# slimevr_mumo_breakout_module_v1_re.net
KiCad netlist of a schematic drawn in EasyEDA Pro
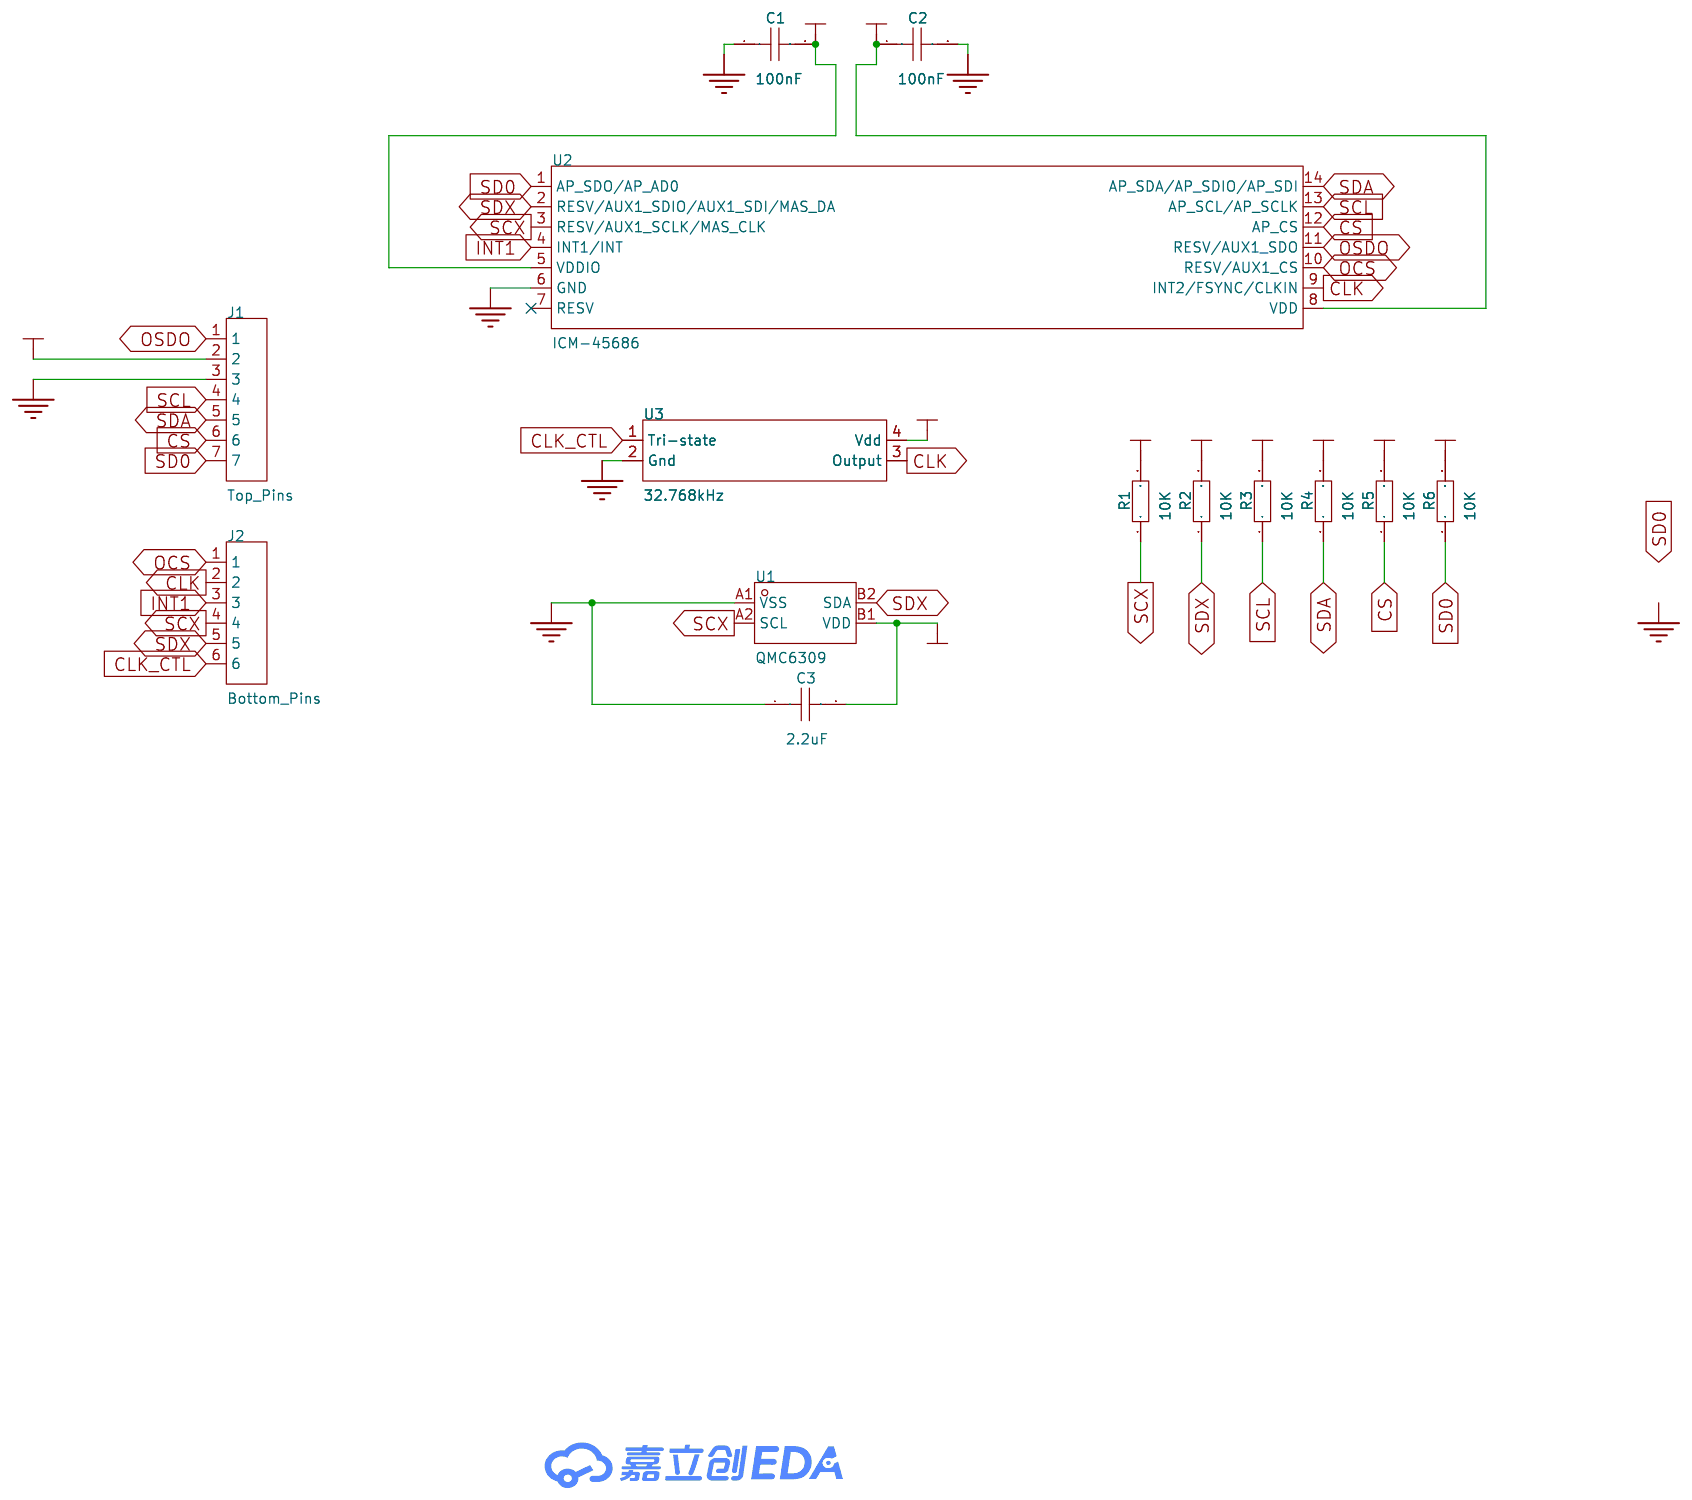
[diagram p0: schematic sheet]

(export (version "E")
  (design (tool "Eeschema 10.0.6"))
  (components
    (comp (ref "C1")
      (value "100nF")
      (footprint "easyedapro:C0603")
      (libsource (lib "easyedapro") (part "Capacitance"))
    )
    (comp (ref "C2")
      (value "100nF")
      (footprint "easyedapro:C0603")
      (libsource (lib "easyedapro") (part "Capacitance"))
    )
    (comp (ref "C3")
      (value "2.2uF")
      (footprint "easyedapro:C0603")
      (libsource (lib "easyedapro") (part "Capacitance"))
    )
    (comp (ref "J1")
      (value "Top_Pins")
      (footprint "easyedapro:HDR-TH_7P-P2.54-V-M")
      (fields
        (field (name "Manufacturer Part") "HB-PH3-25417PB2GOP")
        (field (name "Manufacturer") "HANBO(汉博)")
      )
      (libsource (lib "easyedapro") (part "HB-PH3-25417PB2GOP"))
    )
    (comp (ref "J2")
      (value "Bottom_Pins")
      (footprint "easyedapro:HDR-TH_6P-P2.54-V-M")
      (fields
        (field (name "Manufacturer Part") "HB-PH3-25416PB2GOP")
        (field (name "Manufacturer") "HANBO(汉博)")
      )
      (libsource (lib "easyedapro") (part "HB-PH3-25416PB2GOP"))
    )
    (comp (ref "R1") (value "10K") (footprint "easyedapro:R0603") (libsource (lib "easyedapro") (part "电阻")))
    (comp (ref "R2") (value "10K") (footprint "easyedapro:R0603") (libsource (lib "easyedapro") (part "电阻")))
    (comp (ref "R3") (value "10K") (footprint "easyedapro:R0603") (libsource (lib "easyedapro") (part "电阻")))
    (comp (ref "R4") (value "10K") (footprint "easyedapro:R0603") (libsource (lib "easyedapro") (part "电阻")))
    (comp (ref "R5") (value "10K") (footprint "easyedapro:R0603") (libsource (lib "easyedapro") (part "电阻")))
    (comp (ref "R6") (value "10K") (footprint "easyedapro:R0603") (libsource (lib "easyedapro") (part "电阻")))
    (comp (ref "U1")
      (value "QMC6309")
      (footprint "easyedapro:X1-WLB0808-4_L0.8-W0.8-P0.40-TL")
      (fields (field (name "Manufacturer") "QST(上海矽睿)"))
      (libsource (lib "easyedapro") (part "QMC6309"))
    )
    (comp (ref "U2")
      (value "ICM-45686")
      (footprint "easyedapro:LGA-14_L3.0-W2.5-P0.50-TL")
      (fields (field (name "Manufacturer") "TDK InvenSense(应美盛)"))
      (libsource (lib "easyedapro") (part "ICM-45686"))
    )
    (comp (ref "U3")
      (value "32.768kHz")
      (footprint "easyedapro:OSC-SMD_4P-L3.2-W2.5-BL")
      (description "频率:32.768kHz;工作电压:3.3V;工作电流:70uA;频率稳定度:±10ppm;")
      (fields
        (field (name "Manufacturer Part") "YF4032K76833T8188081")
        (field (name "Manufacturer") "JWT(晶威特)")
      )
      (libsource (lib "easyedapro") (part "YF4032K76833T8188081"))
    )
  )
  (nets
    (net (code "1") (name "+3V3") (class "Default")
      (node (ref "C1") (pin "2") (pinfunction "2_2") (pintype "input"))
      (node (ref "C2") (pin "1") (pinfunction "1_1") (pintype "input"))
      (node (ref "C3") (pin "2") (pinfunction "2_2") (pintype "input"))
      (node (ref "J1") (pin "2") (pinfunction "2_2") (pintype "unspecified"))
      (node (ref "R1") (pin "2") (pinfunction "2_2") (pintype "input"))
      (node (ref "R2") (pin "2") (pinfunction "2_2") (pintype "input"))
      (node (ref "R3") (pin "2") (pinfunction "2_2") (pintype "input"))
      (node (ref "R4") (pin "2") (pinfunction "2_2") (pintype "input"))
      (node (ref "R5") (pin "2") (pinfunction "2_2") (pintype "input"))
      (node (ref "R6") (pin "2") (pinfunction "2_2") (pintype "input"))
      (node (ref "U1") (pin "B1") (pinfunction "VDD_B1") (pintype "unspecified"))
      (node (ref "U2") (pin "5") (pinfunction "VDDIO_5") (pintype "unspecified"))
      (node (ref "U2") (pin "8") (pinfunction "VDD_8") (pintype "unspecified"))
      (node (ref "U3") (pin "4") (pinfunction "Vdd_4") (pintype "unspecified"))
    )
    (net (code "2") (name "CLK") (class "Default")
      (node (ref "J2") (pin "2") (pinfunction "2_2") (pintype "unspecified"))
      (node (ref "U2") (pin "9") (pinfunction "INT2/FSYNC/CLKIN_9") (pintype "unspecified"))
      (node (ref "U3") (pin "3") (pinfunction "Output_3") (pintype "unspecified"))
    )
    (net (code "3") (name "CLK_CTL") (class "Default")
      (node (ref "J2") (pin "6") (pinfunction "6_6") (pintype "unspecified"))
      (node (ref "U3") (pin "1") (pinfunction "Tri-state_1") (pintype "unspecified"))
    )
    (net (code "4") (name "CS") (class "Default")
      (node (ref "J1") (pin "6") (pinfunction "6_6") (pintype "unspecified"))
      (node (ref "R5") (pin "1") (pinfunction "1_1") (pintype "input"))
      (node (ref "U2") (pin "12") (pinfunction "AP_CS_12") (pintype "unspecified"))
    )
    (net (code "5") (name "GND") (class "Default")
      (node (ref "C1") (pin "1") (pinfunction "1_1") (pintype "input"))
      (node (ref "C2") (pin "2") (pinfunction "2_2") (pintype "input"))
      (node (ref "C3") (pin "1") (pinfunction "1_1") (pintype "input"))
      (node (ref "J1") (pin "3") (pinfunction "3_3") (pintype "unspecified"))
      (node (ref "U1") (pin "A1") (pinfunction "VSS_A1") (pintype "unspecified"))
      (node (ref "U2") (pin "6") (pinfunction "GND_6") (pintype "unspecified"))
      (node (ref "U3") (pin "2") (pinfunction "Gnd_2") (pintype "unspecified"))
    )
    (net (code "6") (name "INT1") (class "Default")
      (node (ref "J2") (pin "3") (pinfunction "3_3") (pintype "unspecified"))
      (node (ref "U2") (pin "4") (pinfunction "INT1/INT_4") (pintype "unspecified"))
    )
    (net (code "7") (name "OCS") (class "Default")
      (node (ref "J2") (pin "1") (pinfunction "1_1") (pintype "unspecified"))
      (node (ref "U2") (pin "10") (pinfunction "RESV/AUX1_CS_10") (pintype "unspecified"))
    )
    (net (code "8") (name "OSDO") (class "Default")
      (node (ref "J1") (pin "1") (pinfunction "1_1") (pintype "unspecified"))
      (node (ref "U2") (pin "11") (pinfunction "RESV/AUX1_SDO_11") (pintype "unspecified"))
    )
    (net (code "9") (name "SCL") (class "Default")
      (node (ref "J1") (pin "4") (pinfunction "4_4") (pintype "unspecified"))
      (node (ref "R3") (pin "1") (pinfunction "1_1") (pintype "input"))
      (node (ref "U2") (pin "13") (pinfunction "AP_SCL/AP_SCLK_13") (pintype "unspecified"))
    )
    (net (code "10") (name "SCX") (class "Default")
      (node (ref "J2") (pin "4") (pinfunction "4_4") (pintype "unspecified"))
      (node (ref "R1") (pin "1") (pinfunction "1_1") (pintype "input"))
      (node (ref "U1") (pin "A2") (pinfunction "SCL_A2") (pintype "unspecified"))
      (node (ref "U2") (pin "3") (pinfunction "RESV/AUX1_SCLK/MAS_CLK_3") (pintype "unspecified"))
    )
    (net (code "11") (name "SD0") (class "Default")
      (node (ref "J1") (pin "7") (pinfunction "7_7") (pintype "unspecified"))
      (node (ref "R6") (pin "1") (pinfunction "1_1") (pintype "input"))
      (node (ref "U2") (pin "1") (pinfunction "AP_SDO/AP_AD0_1") (pintype "unspecified"))
    )
    (net (code "12") (name "SDA") (class "Default")
      (node (ref "J1") (pin "5") (pinfunction "5_5") (pintype "unspecified"))
      (node (ref "R4") (pin "1") (pinfunction "1_1") (pintype "input"))
      (node (ref "U2") (pin "14") (pinfunction "AP_SDA/AP_SDIO/AP_SDI_14") (pintype "unspecified"))
    )
    (net (code "13") (name "SDX") (class "Default")
      (node (ref "J2") (pin "5") (pinfunction "5_5") (pintype "unspecified"))
      (node (ref "R2") (pin "1") (pinfunction "1_1") (pintype "input"))
      (node (ref "U1") (pin "B2") (pinfunction "SDA_B2") (pintype "unspecified"))
      (node (ref "U2") (pin "2") (pinfunction "RESV/AUX1_SDIO/AUX1_SDI/MAS_DA_2") (pintype "unspecified"))
    )
    (net (code "14") (name "unconnected-(U2-RESV-Pad7)") (class "Default")
      (node (ref "U2") (pin "7") (pinfunction "RESV_7") (pintype "unspecified+no_connect"))
    )
  )
)
